# UI_Schematic.net
KiCad netlist of a schematic drawn in Altium Designer
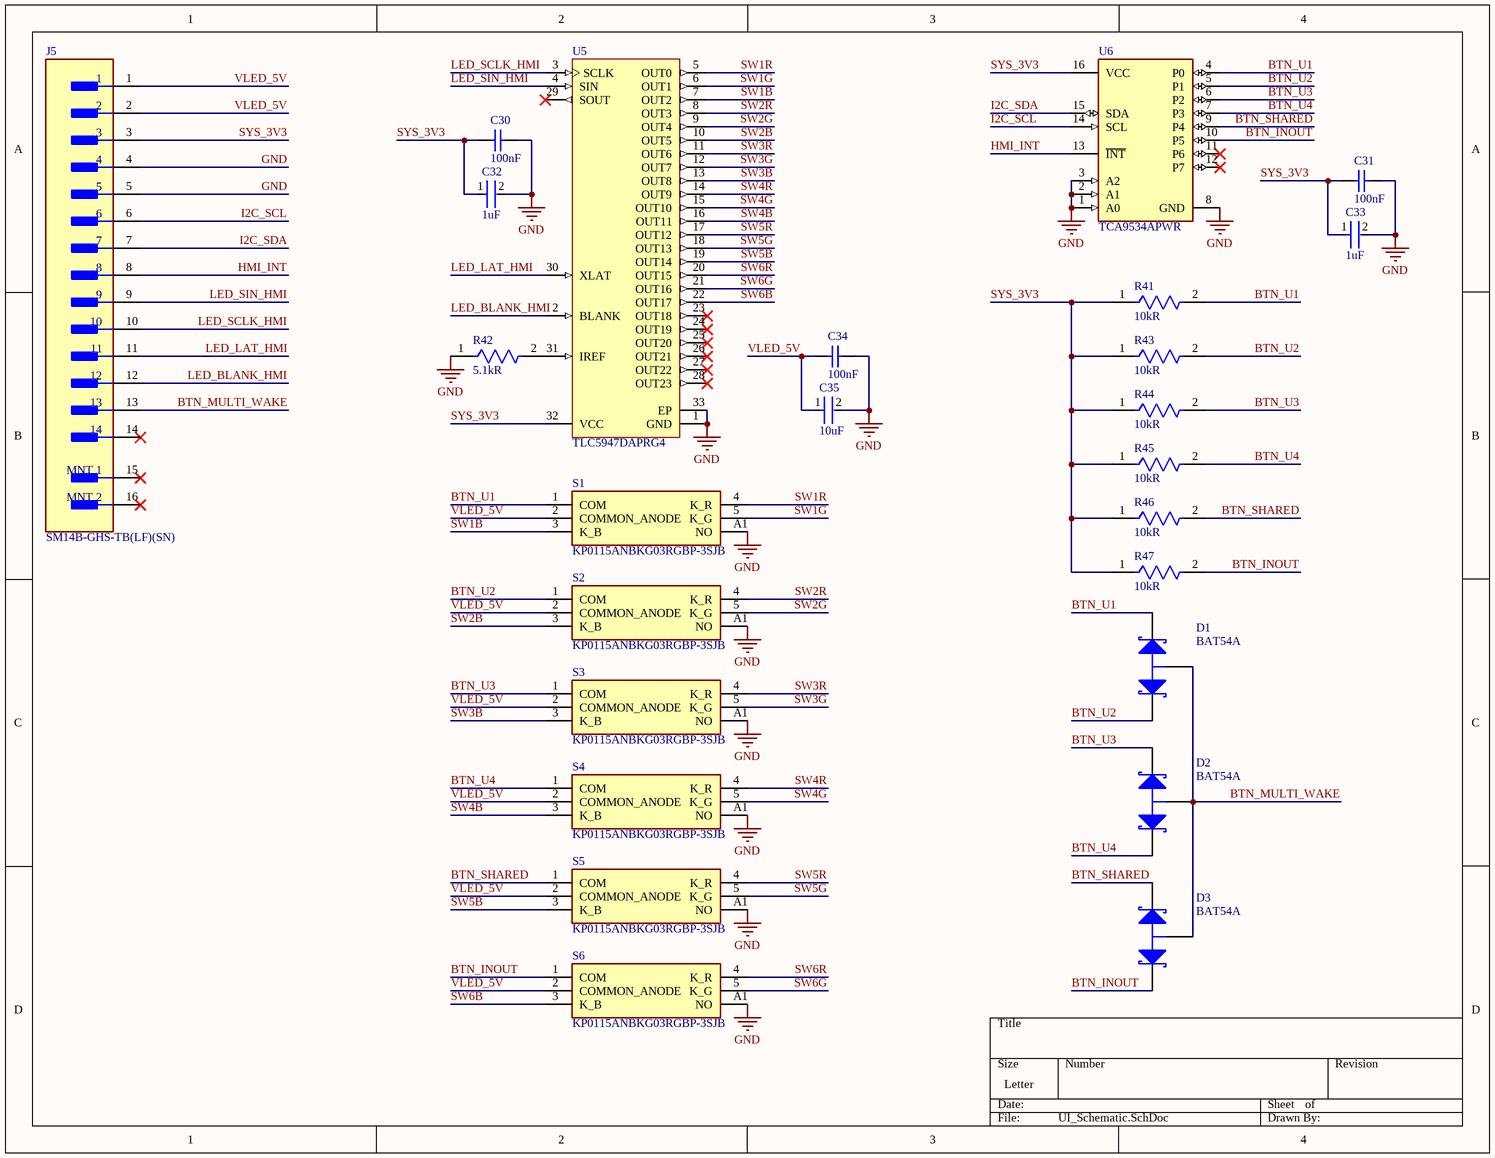
[diagram p0: UI_Schematic.SchDoc]

(export (version "E")
  (design (tool "Eeschema 10.0.6"))
  (components
    (comp (ref "C30")
      (value "100nF")
      (footprint "CAPC1608X90X35ML10T15")
      (description "Chip Capacitor, 100 nF, +/- 10%, 50 V, -55 to 125 degC, 0603 (1608 Metric), RoHS, Tape and Reel")
      (fields (field (name "MANUFACTURER") "Murata"))
      (libsource (lib "Altium Content Vault") (part "CAP-NP-2"))
    )
    (comp (ref "C31")
      (value "100nF")
      (footprint "CAPC1608X90X35ML10T15")
      (description "Chip Capacitor, 100 nF, +/- 10%, 50 V, -55 to 125 degC, 0603 (1608 Metric), RoHS, Tape and Reel")
      (fields (field (name "MANUFACTURER") "Murata"))
      (libsource (lib "Altium Content Vault") (part "CAP-NP-2"))
    )
    (comp (ref "C32")
      (value "1uF")
      (footprint "FP-GRT188-0_1-e0_2_0_5-IPC_C")
      (description "Multi-Layer Ceramic Capacitor 1uF 25V X7R ±10% 0603 Paper T/R")
      (libsource (lib "Altium Content Vault") (part "02cd4be3c70576c341d710602a673aa"))
    )
    (comp (ref "C33")
      (value "1uF")
      (footprint "FP-GRT188-0_1-e0_2_0_5-IPC_C")
      (description "Multi-Layer Ceramic Capacitor 1uF 25V X7R ±10% 0603 Paper T/R")
      (libsource (lib "Altium Content Vault") (part "02cd4be3c70576c341d710602a673aa"))
    )
    (comp (ref "C34")
      (value "100nF")
      (footprint "CAPC1608X90X35ML10T15")
      (description "Chip Capacitor, 100 nF, +/- 10%, 50 V, -55 to 125 degC, 0603 (1608 Metric), RoHS, Tape and Reel")
      (fields (field (name "MANUFACTURER") "Murata"))
      (libsource (lib "Altium Content Vault") (part "CAP-NP-2"))
    )
    (comp (ref "C35")
      (value "10uF")
      (footprint "FP-GRM21B-0_15-IPC_A")
      (description "Chip Multilayer Ceramic Capacitors for General Purpose, 0805, 10uF, X5R, 15%, 20%, 25V")
      (fields (field (name "TOLERANCE") "20%"))
      (libsource (lib "Altium Content Vault") (part "b4654b650e69147ec39a6b967a45e02"))
    )
    (comp (ref "D1")
      (value "BAT54A")
      (footprint "NXP-SOT23-3_V")
      (description "Schottky Barrier Diode, 30 V, 2 uA, -55 to 150 degC, 3-Pin SOT23, RoHS, Tape and Reel")
      (fields (field (name "MANUFACTURER") "NXP Semiconductors"))
      (libsource (lib "Altium Content Vault") (part "NXP-DSKY_K1K2A3-3"))
    )
    (comp (ref "D2")
      (value "BAT54A")
      (footprint "NXP-SOT23-3_V")
      (description "Schottky Barrier Diode, 30 V, 2 uA, -55 to 150 degC, 3-Pin SOT23, RoHS, Tape and Reel")
      (fields (field (name "MANUFACTURER") "NXP Semiconductors"))
      (libsource (lib "Altium Content Vault") (part "NXP-DSKY_K1K2A3-3"))
    )
    (comp (ref "D3")
      (value "BAT54A")
      (footprint "NXP-SOT23-3_V")
      (description "Schottky Barrier Diode, 30 V, 2 uA, -55 to 150 degC, 3-Pin SOT23, RoHS, Tape and Reel")
      (fields (field (name "MANUFACTURER") "NXP Semiconductors"))
      (libsource (lib "Altium Content Vault") (part "NXP-DSKY_K1K2A3-3"))
    )
    (comp (ref "J5")
      (value "SM14B-GHS-TB(LF)(SN)")
      (footprint "FP-SM14B-GHS-TB_LF_SN-MFG")
      (description "CONN HEADER SMD R/A 14POS 1.25MM")
      (libsource (lib "Altium Content Vault") (part "4e16b2d45535132dfc94a0c32fbd9e7"))
    )
    (comp (ref "R41")
      (value "10kR")
      (footprint "FP-AC0603-IPC_A")
      (description "RES 10kΩ 5.00% 0.2W 0603")
      (libsource (lib "Altium Content Vault") (part "1029c3af85768c4190bb7ad29bc67b5"))
    )
    (comp (ref "R42")
      (value "5.1kR")
      (footprint "FP-AT0603-IPC_B")
      (description "Thin Film Chip Resistors Automotive Grade 5.1kΩ 1% 50ppm/°C 0603")
      (libsource (lib "Altium Content Vault") (part "1029c3af85768c4190bb7ad29bc67b5"))
    )
    (comp (ref "R43")
      (value "10kR")
      (footprint "FP-AC0603-IPC_A")
      (description "RES 10kΩ 5.00% 0.2W 0603")
      (libsource (lib "Altium Content Vault") (part "1029c3af85768c4190bb7ad29bc67b5"))
    )
    (comp (ref "R44")
      (value "10kR")
      (footprint "FP-AC0603-IPC_A")
      (description "RES 10kΩ 5.00% 0.2W 0603")
      (libsource (lib "Altium Content Vault") (part "1029c3af85768c4190bb7ad29bc67b5"))
    )
    (comp (ref "R45")
      (value "10kR")
      (footprint "FP-AC0603-IPC_A")
      (description "RES 10kΩ 5.00% 0.2W 0603")
      (libsource (lib "Altium Content Vault") (part "1029c3af85768c4190bb7ad29bc67b5"))
    )
    (comp (ref "R46")
      (value "10kR")
      (footprint "FP-AC0603-IPC_A")
      (description "RES 10kΩ 5.00% 0.2W 0603")
      (libsource (lib "Altium Content Vault") (part "1029c3af85768c4190bb7ad29bc67b5"))
    )
    (comp (ref "R47")
      (value "10kR")
      (footprint "FP-AC0603-IPC_A")
      (description "RES 10kΩ 5.00% 0.2W 0603")
      (libsource (lib "Altium Content Vault") (part "1029c3af85768c4190bb7ad29bc67b5"))
    )
    (comp (ref "S1")
      (value "KP0115ANBKG03RGBP-3SJB")
      (footprint "SamacSys:KP0115ANBKG03RGBP3SJB")
      (description "Switch")
      (fields (field (name "MOUSER PART NUMBER") "633-5ANBKG03RGBP3SJB"))
      (libsource (lib "*") (part "KP0115ANBKG03RGBP-3SJB"))
    )
    (comp (ref "S2")
      (value "KP0115ANBKG03RGBP-3SJB")
      (footprint "SamacSys:KP0115ANBKG03RGBP3SJB")
      (description "Switch")
      (fields (field (name "MOUSER PART NUMBER") "633-5ANBKG03RGBP3SJB"))
      (libsource (lib "*") (part "KP0115ANBKG03RGBP-3SJB"))
    )
    (comp (ref "S3")
      (value "KP0115ANBKG03RGBP-3SJB")
      (footprint "SamacSys:KP0115ANBKG03RGBP3SJB")
      (description "Switch")
      (fields (field (name "MOUSER PART NUMBER") "633-5ANBKG03RGBP3SJB"))
      (libsource (lib "*") (part "KP0115ANBKG03RGBP-3SJB"))
    )
    (comp (ref "S4")
      (value "KP0115ANBKG03RGBP-3SJB")
      (footprint "SamacSys:KP0115ANBKG03RGBP3SJB")
      (description "Switch")
      (fields (field (name "MOUSER PART NUMBER") "633-5ANBKG03RGBP3SJB"))
      (libsource (lib "*") (part "KP0115ANBKG03RGBP-3SJB"))
    )
    (comp (ref "S5")
      (value "KP0115ANBKG03RGBP-3SJB")
      (footprint "SamacSys:KP0115ANBKG03RGBP3SJB")
      (description "Switch")
      (fields (field (name "MOUSER PART NUMBER") "633-5ANBKG03RGBP3SJB"))
      (libsource (lib "*") (part "KP0115ANBKG03RGBP-3SJB"))
    )
    (comp (ref "S6")
      (value "KP0115ANBKG03RGBP-3SJB")
      (footprint "SamacSys:KP0115ANBKG03RGBP3SJB")
      (description "Switch")
      (fields (field (name "MOUSER PART NUMBER") "633-5ANBKG03RGBP3SJB"))
      (libsource (lib "*") (part "KP0115ANBKG03RGBP-3SJB"))
    )
    (comp (ref "U5")
      (value "TLC5947DAPRG4")
      (footprint "TI-DAP32-3810X3710TP_N")
      (fields (field (name "MANUFACTURER") "Texas Instruments"))
      (libsource (lib "Altium Content Vault") (part "TI-TLC5947DAP32-3810X3710TP"))
    )
    (comp (ref "U6")
      (value "TCA9534APWR")
      (footprint "FP-PW0016A-MFG")
      (description "IC I/O EXPANDER I2C 8B 16TSSOP")
      (fields
        (field (name "OCTOPART") "https://octopart.com/tca9534apwr-texas+instruments-50333529")
        (field (name "MANUFACTURER") "Texas Instruments")
      )
      (libsource (lib "Altium Content Vault") (part "0b0800cf057530dbd4e48f5dd6c25fb"))
    )
  )
  (nets
    (net (code "1") (name "/BTN_INOUT") (class "Default")
      (node (ref "D3") (pin "2") (pinfunction "K_2") (pintype "passive"))
      (node (ref "R47") (pin "2") (pinfunction "2_2") (pintype "passive"))
      (node (ref "S6") (pin "1") (pinfunction "COM_1") (pintype "passive"))
      (node (ref "U6") (pin "10") (pinfunction "P5_10") (pintype "bidirectional"))
    )
    (net (code "2") (name "/BTN_MULTI_WAKE") (class "Default")
      (node (ref "D1") (pin "3") (pinfunction "A_3") (pintype "passive"))
      (node (ref "D2") (pin "3") (pinfunction "A_3") (pintype "passive"))
      (node (ref "D3") (pin "3") (pinfunction "A_3") (pintype "passive"))
      (node (ref "J5") (pin "13") (pinfunction "13_13") (pintype "passive"))
    )
    (net (code "3") (name "/BTN_SHARED") (class "Default")
      (node (ref "D3") (pin "1") (pinfunction "K_1") (pintype "passive"))
      (node (ref "R46") (pin "2") (pinfunction "2_2") (pintype "passive"))
      (node (ref "S5") (pin "1") (pinfunction "COM_1") (pintype "passive"))
      (node (ref "U6") (pin "9") (pinfunction "P4_9") (pintype "bidirectional"))
    )
    (net (code "4") (name "/BTN_U1") (class "Default")
      (node (ref "D1") (pin "1") (pinfunction "K_1") (pintype "passive"))
      (node (ref "R41") (pin "2") (pinfunction "2_2") (pintype "passive"))
      (node (ref "S1") (pin "1") (pinfunction "COM_1") (pintype "passive"))
      (node (ref "U6") (pin "4") (pinfunction "P0_4") (pintype "bidirectional"))
    )
    (net (code "5") (name "/BTN_U2") (class "Default")
      (node (ref "D1") (pin "2") (pinfunction "K_2") (pintype "passive"))
      (node (ref "R43") (pin "2") (pinfunction "2_2") (pintype "passive"))
      (node (ref "S2") (pin "1") (pinfunction "COM_1") (pintype "passive"))
      (node (ref "U6") (pin "5") (pinfunction "P1_5") (pintype "bidirectional"))
    )
    (net (code "6") (name "/BTN_U3") (class "Default")
      (node (ref "D2") (pin "1") (pinfunction "K_1") (pintype "passive"))
      (node (ref "R44") (pin "2") (pinfunction "2_2") (pintype "passive"))
      (node (ref "S3") (pin "1") (pinfunction "COM_1") (pintype "passive"))
      (node (ref "U6") (pin "6") (pinfunction "P2_6") (pintype "bidirectional"))
    )
    (net (code "7") (name "/BTN_U4") (class "Default")
      (node (ref "D2") (pin "2") (pinfunction "K_2") (pintype "passive"))
      (node (ref "R45") (pin "2") (pinfunction "2_2") (pintype "passive"))
      (node (ref "S4") (pin "1") (pinfunction "COM_1") (pintype "passive"))
      (node (ref "U6") (pin "7") (pinfunction "P3_7") (pintype "bidirectional"))
    )
    (net (code "8") (name "/HMI_INT") (class "Default")
      (node (ref "J5") (pin "8") (pinfunction "8_8") (pintype "passive"))
      (node (ref "U6") (pin "13") (pinfunction "~{INT}_13") (pintype "open_collector"))
    )
    (net (code "9") (name "/I2C_SCL") (class "Default")
      (node (ref "J5") (pin "6") (pinfunction "6_6") (pintype "passive"))
      (node (ref "U6") (pin "14") (pinfunction "SCL_14") (pintype "input"))
    )
    (net (code "10") (name "/I2C_SDA") (class "Default")
      (node (ref "J5") (pin "7") (pinfunction "7_7") (pintype "passive"))
      (node (ref "U6") (pin "15") (pinfunction "SDA_15") (pintype "bidirectional"))
    )
    (net (code "11") (name "/LED_BLANK_HMI") (class "Default")
      (node (ref "J5") (pin "12") (pinfunction "12_12") (pintype "passive"))
      (node (ref "U5") (pin "2") (pinfunction "BLANK_2") (pintype "input"))
    )
    (net (code "12") (name "/LED_LAT_HMI") (class "Default")
      (node (ref "J5") (pin "11") (pinfunction "11_11") (pintype "passive"))
      (node (ref "U5") (pin "30") (pinfunction "XLAT_30") (pintype "input"))
    )
    (net (code "13") (name "/LED_SCLK_HMI") (class "Default")
      (node (ref "J5") (pin "10") (pinfunction "10_10") (pintype "passive"))
      (node (ref "U5") (pin "3") (pinfunction "SCLK_3") (pintype "input"))
    )
    (net (code "14") (name "/LED_SIN_HMI") (class "Default")
      (node (ref "J5") (pin "9") (pinfunction "9_9") (pintype "passive"))
      (node (ref "U5") (pin "4") (pinfunction "SIN_4") (pintype "input"))
    )
    (net (code "15") (name "/SW1B") (class "Default")
      (node (ref "S1") (pin "3") (pinfunction "K_B_3") (pintype "passive"))
      (node (ref "U5") (pin "7") (pinfunction "OUT2_7") (pintype "output"))
    )
    (net (code "16") (name "/SW1G") (class "Default")
      (node (ref "S1") (pin "5") (pinfunction "K_G_5") (pintype "passive"))
      (node (ref "U5") (pin "6") (pinfunction "OUT1_6") (pintype "output"))
    )
    (net (code "17") (name "/SW1R") (class "Default")
      (node (ref "S1") (pin "4") (pinfunction "K_R_4") (pintype "passive"))
      (node (ref "U5") (pin "5") (pinfunction "OUT0_5") (pintype "output"))
    )
    (net (code "18") (name "/SW2B") (class "Default")
      (node (ref "S2") (pin "3") (pinfunction "K_B_3") (pintype "passive"))
      (node (ref "U5") (pin "10") (pinfunction "OUT5_10") (pintype "output"))
    )
    (net (code "19") (name "/SW2G") (class "Default")
      (node (ref "S2") (pin "5") (pinfunction "K_G_5") (pintype "passive"))
      (node (ref "U5") (pin "9") (pinfunction "OUT4_9") (pintype "output"))
    )
    (net (code "20") (name "/SW2R") (class "Default")
      (node (ref "S2") (pin "4") (pinfunction "K_R_4") (pintype "passive"))
      (node (ref "U5") (pin "8") (pinfunction "OUT3_8") (pintype "output"))
    )
    (net (code "21") (name "/SW3B") (class "Default")
      (node (ref "S3") (pin "3") (pinfunction "K_B_3") (pintype "passive"))
      (node (ref "U5") (pin "13") (pinfunction "OUT8_13") (pintype "output"))
    )
    (net (code "22") (name "/SW3G") (class "Default")
      (node (ref "S3") (pin "5") (pinfunction "K_G_5") (pintype "passive"))
      (node (ref "U5") (pin "12") (pinfunction "OUT7_12") (pintype "output"))
    )
    (net (code "23") (name "/SW3R") (class "Default")
      (node (ref "S3") (pin "4") (pinfunction "K_R_4") (pintype "passive"))
      (node (ref "U5") (pin "11") (pinfunction "OUT6_11") (pintype "output"))
    )
    (net (code "24") (name "/SW4B") (class "Default")
      (node (ref "S4") (pin "3") (pinfunction "K_B_3") (pintype "passive"))
      (node (ref "U5") (pin "16") (pinfunction "OUT11_16") (pintype "output"))
    )
    (net (code "25") (name "/SW4G") (class "Default")
      (node (ref "S4") (pin "5") (pinfunction "K_G_5") (pintype "passive"))
      (node (ref "U5") (pin "15") (pinfunction "OUT10_15") (pintype "output"))
    )
    (net (code "26") (name "/SW4R") (class "Default")
      (node (ref "S4") (pin "4") (pinfunction "K_R_4") (pintype "passive"))
      (node (ref "U5") (pin "14") (pinfunction "OUT9_14") (pintype "output"))
    )
    (net (code "27") (name "/SW5B") (class "Default")
      (node (ref "S5") (pin "3") (pinfunction "K_B_3") (pintype "passive"))
      (node (ref "U5") (pin "19") (pinfunction "OUT14_19") (pintype "output"))
    )
    (net (code "28") (name "/SW5G") (class "Default")
      (node (ref "S5") (pin "5") (pinfunction "K_G_5") (pintype "passive"))
      (node (ref "U5") (pin "18") (pinfunction "OUT13_18") (pintype "output"))
    )
    (net (code "29") (name "/SW5R") (class "Default")
      (node (ref "S5") (pin "4") (pinfunction "K_R_4") (pintype "passive"))
      (node (ref "U5") (pin "17") (pinfunction "OUT12_17") (pintype "output"))
    )
    (net (code "30") (name "/SW6B") (class "Default")
      (node (ref "S6") (pin "3") (pinfunction "K_B_3") (pintype "passive"))
      (node (ref "U5") (pin "22") (pinfunction "OUT17_22") (pintype "output"))
    )
    (net (code "31") (name "/SW6G") (class "Default")
      (node (ref "S6") (pin "5") (pinfunction "K_G_5") (pintype "passive"))
      (node (ref "U5") (pin "21") (pinfunction "OUT16_21") (pintype "output"))
    )
    (net (code "32") (name "/SW6R") (class "Default")
      (node (ref "S6") (pin "4") (pinfunction "K_R_4") (pintype "passive"))
      (node (ref "U5") (pin "20") (pinfunction "OUT15_20") (pintype "output"))
    )
    (net (code "33") (name "/SYS_3V3") (class "Default")
      (node (ref "C30") (pin "2") (pinfunction "2_2") (pintype "passive"))
      (node (ref "C31") (pin "2") (pinfunction "2_2") (pintype "passive"))
      (node (ref "C32") (pin "1") (pinfunction "1_1") (pintype "passive"))
      (node (ref "C33") (pin "1") (pinfunction "1_1") (pintype "passive"))
      (node (ref "J5") (pin "3") (pinfunction "3_3") (pintype "passive"))
      (node (ref "R41") (pin "1") (pinfunction "1_1") (pintype "passive"))
      (node (ref "R43") (pin "1") (pinfunction "1_1") (pintype "passive"))
      (node (ref "R44") (pin "1") (pinfunction "1_1") (pintype "passive"))
      (node (ref "R45") (pin "1") (pinfunction "1_1") (pintype "passive"))
      (node (ref "R46") (pin "1") (pinfunction "1_1") (pintype "passive"))
      (node (ref "R47") (pin "1") (pinfunction "1_1") (pintype "passive"))
      (node (ref "U5") (pin "32") (pinfunction "VCC_32") (pintype "power_in"))
      (node (ref "U6") (pin "16") (pinfunction "VCC_16") (pintype "power_in"))
    )
    (net (code "34") (name "/VLED_5V") (class "Default")
      (node (ref "C34") (pin "2") (pinfunction "2_2") (pintype "passive"))
      (node (ref "C35") (pin "1") (pinfunction "1_1") (pintype "passive"))
      (node (ref "J5") (pin "1") (pinfunction "1_1") (pintype "passive"))
      (node (ref "J5") (pin "2") (pinfunction "2_2") (pintype "passive"))
      (node (ref "S1") (pin "2") (pinfunction "COMMON_ANODE_2") (pintype "passive"))
      (node (ref "S2") (pin "2") (pinfunction "COMMON_ANODE_2") (pintype "passive"))
      (node (ref "S3") (pin "2") (pinfunction "COMMON_ANODE_2") (pintype "passive"))
      (node (ref "S4") (pin "2") (pinfunction "COMMON_ANODE_2") (pintype "passive"))
      (node (ref "S5") (pin "2") (pinfunction "COMMON_ANODE_2") (pintype "passive"))
      (node (ref "S6") (pin "2") (pinfunction "COMMON_ANODE_2") (pintype "passive"))
    )
    (net (code "35") (name "GND") (class "Default")
      (node (ref "C30") (pin "1") (pinfunction "1_1") (pintype "passive"))
      (node (ref "C31") (pin "1") (pinfunction "1_1") (pintype "passive"))
      (node (ref "C32") (pin "2") (pinfunction "2_2") (pintype "passive"))
      (node (ref "C33") (pin "2") (pinfunction "2_2") (pintype "passive"))
      (node (ref "C34") (pin "1") (pinfunction "1_1") (pintype "passive"))
      (node (ref "C35") (pin "2") (pinfunction "2_2") (pintype "passive"))
      (node (ref "J5") (pin "4") (pinfunction "4_4") (pintype "passive"))
      (node (ref "J5") (pin "5") (pinfunction "5_5") (pintype "passive"))
      (node (ref "R42") (pin "1") (pinfunction "1_1") (pintype "passive"))
      (node (ref "S1") (pin "A1") (pinfunction "NO_A1") (pintype "passive"))
      (node (ref "S2") (pin "A1") (pinfunction "NO_A1") (pintype "passive"))
      (node (ref "S3") (pin "A1") (pinfunction "NO_A1") (pintype "passive"))
      (node (ref "S4") (pin "A1") (pinfunction "NO_A1") (pintype "passive"))
      (node (ref "S5") (pin "A1") (pinfunction "NO_A1") (pintype "passive"))
      (node (ref "S6") (pin "A1") (pinfunction "NO_A1") (pintype "passive"))
      (node (ref "U5") (pin "1") (pinfunction "GND_1") (pintype "power_in"))
      (node (ref "U5") (pin "33") (pinfunction "EP_33") (pintype "power_in"))
      (node (ref "U6") (pin "1") (pinfunction "A0_1") (pintype "input"))
      (node (ref "U6") (pin "2") (pinfunction "A1_2") (pintype "input"))
      (node (ref "U6") (pin "3") (pinfunction "A2_3") (pintype "input"))
      (node (ref "U6") (pin "8") (pinfunction "GND_8") (pintype "power_in"))
    )
    (net (code "36") (name "Net-(U5-IREF)") (class "Default")
      (node (ref "R42") (pin "2") (pinfunction "2_2") (pintype "passive"))
      (node (ref "U5") (pin "31") (pinfunction "IREF_31") (pintype "input"))
    )
    (net (code "37") (name "unconnected-(J5-MNT_1-Pad15)") (class "Default")
      (node (ref "J5") (pin "15") (pinfunction "MNT_1_15") (pintype "passive+no_connect"))
    )
    (net (code "38") (name "unconnected-(J5-MNT_2-Pad16)") (class "Default")
      (node (ref "J5") (pin "16") (pinfunction "MNT_2_16") (pintype "passive+no_connect"))
    )
    (net (code "39") (name "unconnected-(J5-Pad14)") (class "Default")
      (node (ref "J5") (pin "14") (pinfunction "14_14") (pintype "passive+no_connect"))
    )
    (net (code "40") (name "unconnected-(U5-OUT18-Pad23)") (class "Default")
      (node (ref "U5") (pin "23") (pinfunction "OUT18_23") (pintype "output+no_connect"))
    )
    (net (code "41") (name "unconnected-(U5-OUT19-Pad24)") (class "Default")
      (node (ref "U5") (pin "24") (pinfunction "OUT19_24") (pintype "output+no_connect"))
    )
    (net (code "42") (name "unconnected-(U5-OUT20-Pad25)") (class "Default")
      (node (ref "U5") (pin "25") (pinfunction "OUT20_25") (pintype "output+no_connect"))
    )
    (net (code "43") (name "unconnected-(U5-OUT21-Pad26)") (class "Default")
      (node (ref "U5") (pin "26") (pinfunction "OUT21_26") (pintype "output+no_connect"))
    )
    (net (code "44") (name "unconnected-(U5-OUT22-Pad27)") (class "Default")
      (node (ref "U5") (pin "27") (pinfunction "OUT22_27") (pintype "output+no_connect"))
    )
    (net (code "45") (name "unconnected-(U5-OUT23-Pad28)") (class "Default")
      (node (ref "U5") (pin "28") (pinfunction "OUT23_28") (pintype "output+no_connect"))
    )
    (net (code "46") (name "unconnected-(U5-SOUT-Pad29)") (class "Default")
      (node (ref "U5") (pin "29") (pinfunction "SOUT_29") (pintype "output+no_connect"))
    )
    (net (code "47") (name "unconnected-(U6-P6-Pad11)") (class "Default")
      (node (ref "U6") (pin "11") (pinfunction "P6_11") (pintype "bidirectional+no_connect"))
    )
    (net (code "48") (name "unconnected-(U6-P7-Pad12)") (class "Default")
      (node (ref "U6") (pin "12") (pinfunction "P7_12") (pintype "bidirectional+no_connect"))
    )
  )
)
